# dc-dc-converter.net
KiCad netlist of a schematic drawn in EAGLE
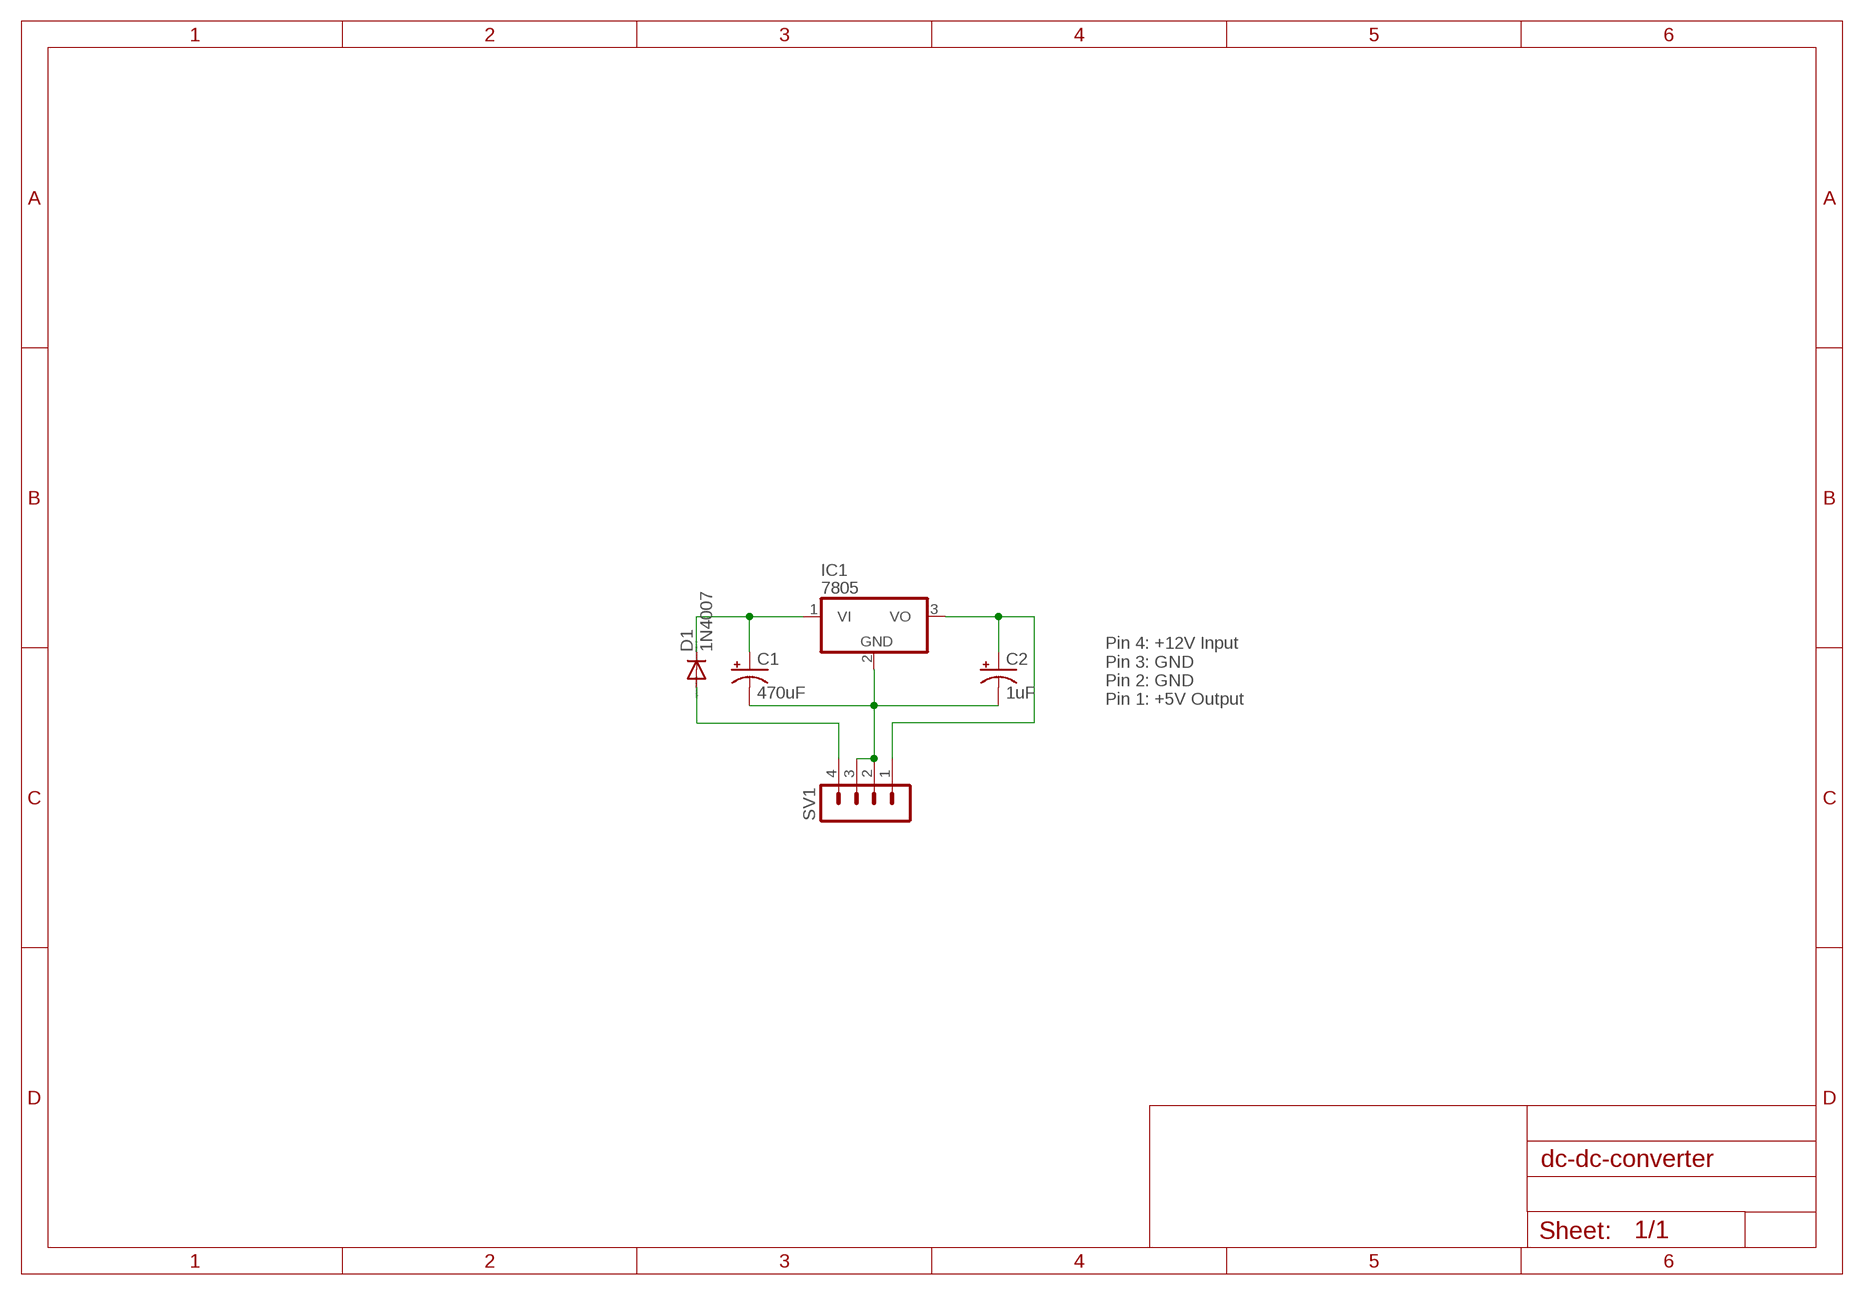
[diagram p0: schematic, sheet 1]

(export (version "E")
  (design (tool "Eeschema 10.0.6"))
  (components
    (comp (ref "C1")
      (value "470uF")
      (footprint "eagle-import:B45181A")
      (libsource (lib "eagle-import") (part "CPOL-USB45181A"))
    )
    (comp (ref "C2")
      (value "1uF")
      (footprint "eagle-import:B45181A")
      (libsource (lib "eagle-import") (part "CPOL-USB45181A"))
    )
    (comp (ref "D1")
      (value "1N4007")
      (footprint "eagle-import:DO41-10")
      (libsource (lib "eagle-import") (part "1N4004"))
    )
    (comp (ref "IC1")
      (value "7805")
      (footprint "eagle-import:TO220V")
      (libsource (lib "eagle-import") (part "78TV05"))
    )
    (comp (ref "SV1")
      (value "MA04-1")
      (footprint "eagle-import:MA04-1")
      (libsource (lib "eagle-import") (part "MA04-1"))
    )
  )
  (nets
    (net (code "1") (name "Net-(D1-PadA)") (class "Default")
      (node (ref "D1") (pin "A") (pinfunction "A_A") (pintype "passive"))
      (node (ref "SV1") (pin "4") (pinfunction "4_4") (pintype "passive"))
    )
    (net (code "2") (name "Net-(IC1-GND)") (class "Default")
      (node (ref "C1") (pin "-") (pinfunction "-_-") (pintype "passive"))
      (node (ref "C2") (pin "-") (pinfunction "-_-") (pintype "passive"))
      (node (ref "IC1") (pin "2") (pinfunction "GND_2") (pintype "passive"))
      (node (ref "SV1") (pin "2") (pinfunction "2_2") (pintype "passive"))
      (node (ref "SV1") (pin "3") (pinfunction "3_3") (pintype "passive"))
    )
    (net (code "3") (name "Net-(IC1-VI)") (class "Default")
      (node (ref "C1") (pin "+") (pinfunction "+_+") (pintype "passive"))
      (node (ref "D1") (pin "C") (pinfunction "C_C") (pintype "passive"))
      (node (ref "IC1") (pin "1") (pinfunction "VI_1") (pintype "input"))
    )
    (net (code "4") (name "Net-(IC1-VO)") (class "Default")
      (node (ref "C2") (pin "+") (pinfunction "+_+") (pintype "passive"))
      (node (ref "IC1") (pin "3") (pinfunction "VO_3") (pintype "passive"))
      (node (ref "SV1") (pin "1") (pinfunction "1_1") (pintype "passive"))
    )
  )
)
